# VCO_SCH.net
KiCad netlist of a schematic drawn in Altium Designer
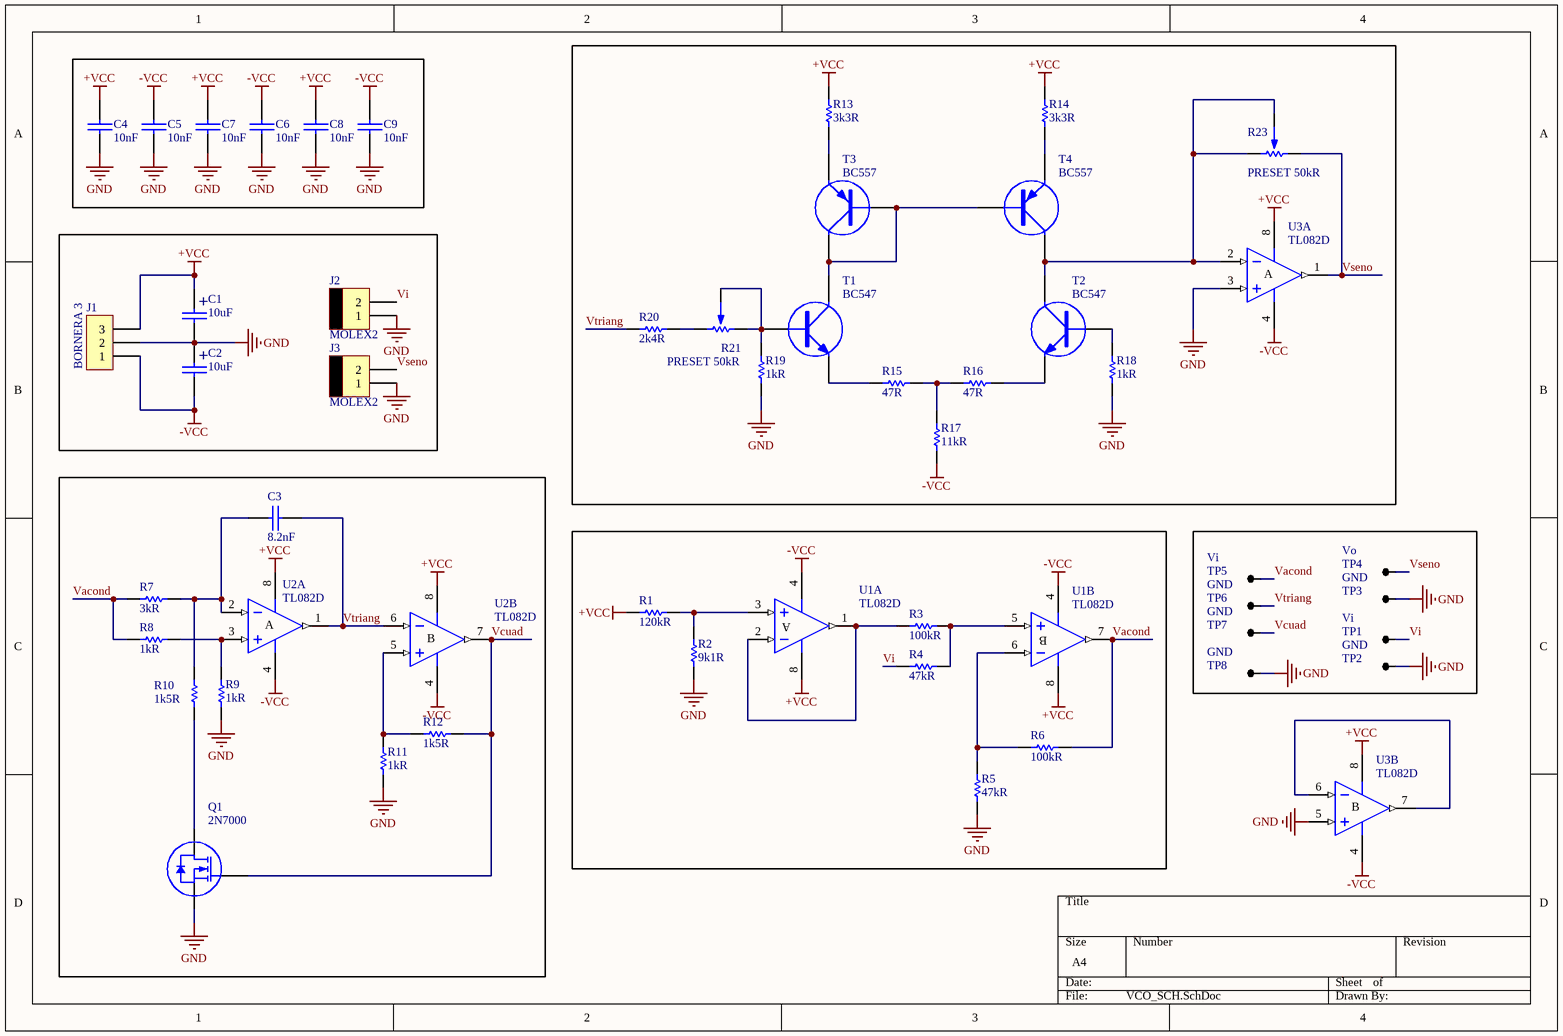
[diagram p0: VCO_SCH.SchDoc]

(export (version "E")
  (design (tool "Eeschema 10.0.6"))
  (components
    (comp (ref "C1") (value "10uF") (footprint "CAP100RP") (libsource (lib "LIBEBAL") (part "CAPPOL")))
    (comp (ref "C2") (value "10uF") (footprint "CAP100RP") (libsource (lib "LIBEBAL") (part "CAPPOL")))
    (comp (ref "C3") (value "8.2nF") (footprint "0805") (libsource (lib "LIBEBAL") (part "CAP")))
    (comp (ref "C4") (value "10nF") (footprint "0805") (libsource (lib "LIBEBAL") (part "CAP")))
    (comp (ref "C5") (value "10nF") (footprint "0805") (libsource (lib "LIBEBAL") (part "CAP")))
    (comp (ref "C6") (value "10nF") (footprint "0805") (libsource (lib "LIBEBAL") (part "CAP")))
    (comp (ref "C7") (value "10nF") (footprint "0805") (libsource (lib "LIBEBAL") (part "CAP")))
    (comp (ref "C8") (value "10nF") (footprint "0805") (libsource (lib "LIBEBAL") (part "CAP")))
    (comp (ref "C9") (value "10nF") (footprint "0805") (libsource (lib "LIBEBAL") (part "CAP")))
    (comp (ref "J1")
      (value "BORNERA 3")
      (footprint "BORNERA3")
      (libsource (lib "LIBEBAL") (part "BORNERA 3"))
    )
    (comp (ref "J2") (value "MOLEX2") (footprint "MOLEX2") (libsource (lib "LIBEBAL") (part "MOLEX2")))
    (comp (ref "J3") (value "MOLEX2") (footprint "MOLEX2") (libsource (lib "LIBEBAL") (part "MOLEX2")))
    (comp (ref "Q1") (value "2N7000") (footprint "TO92") (libsource (lib "LIBEBAL") (part "MOSFET N")))
    (comp (ref "R1") (value "120kR") (footprint "0805") (libsource (lib "LIBEBAL") (part "RES")))
    (comp (ref "R2") (value "9k1R") (footprint "0805") (libsource (lib "LIBEBAL") (part "RES")))
    (comp (ref "R3") (value "100kR") (footprint "0805") (libsource (lib "LIBEBAL") (part "RES")))
    (comp (ref "R4") (value "47kR") (footprint "0805") (libsource (lib "LIBEBAL") (part "RES")))
    (comp (ref "R5") (value "47kR") (footprint "0805") (libsource (lib "LIBEBAL") (part "RES")))
    (comp (ref "R6") (value "100kR") (footprint "0805") (libsource (lib "LIBEBAL") (part "RES")))
    (comp (ref "R7") (value "3kR") (footprint "0805") (libsource (lib "LIBEBAL") (part "RES")))
    (comp (ref "R8") (value "1kR") (footprint "0805") (libsource (lib "LIBEBAL") (part "RES")))
    (comp (ref "R9") (value "1kR") (footprint "0805") (libsource (lib "LIBEBAL") (part "RES")))
    (comp (ref "R10") (value "1k5R") (footprint "0805") (libsource (lib "LIBEBAL") (part "RES")))
    (comp (ref "R11") (value "1kR") (footprint "0805") (libsource (lib "LIBEBAL") (part "RES")))
    (comp (ref "R12") (value "1k5R") (footprint "0805") (libsource (lib "LIBEBAL") (part "RES")))
    (comp (ref "R13") (value "3k3R") (footprint "0805") (libsource (lib "LIBEBAL") (part "RES")))
    (comp (ref "R14") (value "3k3R") (footprint "0805") (libsource (lib "LIBEBAL") (part "RES")))
    (comp (ref "R15") (value "47R") (footprint "0805") (libsource (lib "LIBEBAL") (part "RES")))
    (comp (ref "R16") (value "47R") (footprint "0805") (libsource (lib "LIBEBAL") (part "RES")))
    (comp (ref "R17") (value "11kR") (footprint "0805") (libsource (lib "LIBEBAL") (part "RES")))
    (comp (ref "R18") (value "1kR") (footprint "0805") (libsource (lib "LIBEBAL") (part "RES")))
    (comp (ref "R19") (value "1kR") (footprint "0805") (libsource (lib "LIBEBAL") (part "RES")))
    (comp (ref "R20") (value "2k4R") (footprint "0805") (libsource (lib "LIBEBAL") (part "RES")))
    (comp (ref "R21")
      (value "PRESET 50kR")
      (footprint "PRESET V")
      (libsource (lib "LIBEBAL") (part "PRESET"))
    )
    (comp (ref "R23")
      (value "PRESET 50kR")
      (footprint "PRESET V")
      (libsource (lib "LIBEBAL") (part "PRESET"))
    )
    (comp (ref "T1") (value "BC547") (footprint "TO92") (libsource (lib "LIBEBAL") (part "TRANSISTOR NPN")))
    (comp (ref "T2") (value "BC547") (footprint "TO92") (libsource (lib "LIBEBAL") (part "TRANSISTOR NPN")))
    (comp (ref "T3") (value "BC557") (footprint "TO92") (libsource (lib "LIBEBAL") (part "TRANSISTOR PNP")))
    (comp (ref "T4") (value "BC557") (footprint "TO92") (libsource (lib "LIBEBAL") (part "TRANSISTOR PNP")))
    (comp (ref "TP1") (value "Vi") (footprint "TPTH") (libsource (lib "LIBEBAL") (part "TP")))
    (comp (ref "TP2") (value "GND") (footprint "TPTH") (libsource (lib "LIBEBAL") (part "TP")))
    (comp (ref "TP3") (value "GND") (footprint "TPTH") (libsource (lib "LIBEBAL") (part "TP")))
    (comp (ref "TP4") (value "Vo") (footprint "TPTH") (libsource (lib "LIBEBAL") (part "TP")))
    (comp (ref "TP5") (value "Vi") (footprint "TPTH") (libsource (lib "LIBEBAL") (part "TP")))
    (comp (ref "TP6") (value "GND") (footprint "TPTH") (libsource (lib "LIBEBAL") (part "TP")))
    (comp (ref "TP7") (value "GND") (footprint "TPTH") (libsource (lib "LIBEBAL") (part "TP")))
    (comp (ref "TP8") (value "GND") (footprint "TPTH") (libsource (lib "LIBEBAL") (part "TP")))
    (comp (ref "U1")
      (value "TL082D")
      (footprint "SOIC8")
      (description "JFET-Input Operational Amplifier")
      (libsource (lib "TI Operational Amplifier") (part "TL082D"))
    )
    (comp (ref "U2")
      (value "TL082D")
      (footprint "SOIC8")
      (description "JFET-Input Operational Amplifier")
      (libsource (lib "TI Operational Amplifier") (part "TL082D"))
    )
    (comp (ref "U3")
      (value "TL082D")
      (footprint "SOIC8")
      (description "JFET-Input Operational Amplifier")
      (libsource (lib "TI Operational Amplifier") (part "TL082D"))
    )
  )
  (nets
    (net (code "1") (name "+VCC") (class "Default")
      (node (ref "C1") (pin "1") (pinfunction "1_1") (pintype "passive"))
      (node (ref "C4") (pin "2") (pinfunction "2_2") (pintype "passive"))
      (node (ref "C7") (pin "2") (pinfunction "2_2") (pintype "passive"))
      (node (ref "C8") (pin "2") (pinfunction "2_2") (pintype "passive"))
      (node (ref "J1") (pin "3") (pinfunction "3_3") (pintype "passive"))
      (node (ref "R1") (pin "1") (pinfunction "1_1") (pintype "passive"))
      (node (ref "R13") (pin "1") (pinfunction "1_1") (pintype "passive"))
      (node (ref "R14") (pin "1") (pinfunction "1_1") (pintype "passive"))
      (node (ref "U1") (pin "8") (pinfunction "V+_8") (pintype "power_in"))
      (node (ref "U2") (pin "8") (pinfunction "V+_8") (pintype "power_in"))
      (node (ref "U3") (pin "8") (pinfunction "V+_8") (pintype "power_in"))
    )
    (net (code "2") (name "-VCC") (class "Default")
      (node (ref "C2") (pin "2") (pinfunction "2_2") (pintype "passive"))
      (node (ref "C5") (pin "2") (pinfunction "2_2") (pintype "passive"))
      (node (ref "C6") (pin "2") (pinfunction "2_2") (pintype "passive"))
      (node (ref "C9") (pin "2") (pinfunction "2_2") (pintype "passive"))
      (node (ref "J1") (pin "1") (pinfunction "1_1") (pintype "passive"))
      (node (ref "R17") (pin "1") (pinfunction "1_1") (pintype "passive"))
      (node (ref "U1") (pin "4") (pinfunction "V-_4") (pintype "power_in"))
      (node (ref "U2") (pin "4") (pinfunction "V-_4") (pintype "power_in"))
      (node (ref "U3") (pin "4") (pinfunction "V-_4") (pintype "power_in"))
    )
    (net (code "3") (name "/Vacond") (class "Default")
      (node (ref "R6") (pin "2") (pinfunction "2_2") (pintype "passive"))
      (node (ref "R7") (pin "1") (pinfunction "1_1") (pintype "passive"))
      (node (ref "R8") (pin "1") (pinfunction "1_1") (pintype "passive"))
      (node (ref "TP5") (pin "1") (pinfunction "1_1") (pintype "passive"))
      (node (ref "U1") (pin "7") (pinfunction "OUT_7") (pintype "output"))
    )
    (net (code "4") (name "/Vcuad") (class "Default")
      (node (ref "Q1") (pin "1") (pinfunction "G_1") (pintype "passive"))
      (node (ref "R12") (pin "2") (pinfunction "2_2") (pintype "passive"))
      (node (ref "TP7") (pin "1") (pinfunction "1_1") (pintype "passive"))
      (node (ref "U2") (pin "7") (pinfunction "OUT_7") (pintype "output"))
    )
    (net (code "5") (name "/Vi") (class "Default")
      (node (ref "J2") (pin "2") (pinfunction "2_2") (pintype "passive"))
      (node (ref "R4") (pin "1") (pinfunction "1_1") (pintype "passive"))
      (node (ref "TP1") (pin "1") (pinfunction "1_1") (pintype "passive"))
    )
    (net (code "6") (name "/Vseno") (class "Default")
      (node (ref "J3") (pin "2") (pinfunction "2_2") (pintype "passive"))
      (node (ref "R23") (pin "3") (pinfunction "3_3") (pintype "passive"))
      (node (ref "TP4") (pin "1") (pinfunction "1_1") (pintype "passive"))
      (node (ref "U3") (pin "1") (pinfunction "OUT_1") (pintype "output"))
    )
    (net (code "7") (name "/Vtriang") (class "Default")
      (node (ref "C3") (pin "2") (pinfunction "2_2") (pintype "passive"))
      (node (ref "R20") (pin "1") (pinfunction "1_1") (pintype "passive"))
      (node (ref "TP6") (pin "1") (pinfunction "1_1") (pintype "passive"))
      (node (ref "U2") (pin "1") (pinfunction "OUT_1") (pintype "output"))
      (node (ref "U2") (pin "6") (pinfunction "IN-_6") (pintype "input"))
    )
    (net (code "8") (name "GND") (class "Default")
      (node (ref "C1") (pin "2") (pinfunction "2_2") (pintype "passive"))
      (node (ref "C2") (pin "1") (pinfunction "1_1") (pintype "passive"))
      (node (ref "C4") (pin "1") (pinfunction "1_1") (pintype "passive"))
      (node (ref "C5") (pin "1") (pinfunction "1_1") (pintype "passive"))
      (node (ref "C6") (pin "1") (pinfunction "1_1") (pintype "passive"))
      (node (ref "C7") (pin "1") (pinfunction "1_1") (pintype "passive"))
      (node (ref "C8") (pin "1") (pinfunction "1_1") (pintype "passive"))
      (node (ref "C9") (pin "1") (pinfunction "1_1") (pintype "passive"))
      (node (ref "J1") (pin "2") (pinfunction "2_2") (pintype "passive"))
      (node (ref "J2") (pin "1") (pinfunction "1_1") (pintype "passive"))
      (node (ref "J3") (pin "1") (pinfunction "1_1") (pintype "passive"))
      (node (ref "Q1") (pin "3") (pinfunction "S_3") (pintype "passive"))
      (node (ref "R11") (pin "2") (pinfunction "2_2") (pintype "passive"))
      (node (ref "R18") (pin "1") (pinfunction "1_1") (pintype "passive"))
      (node (ref "R19") (pin "1") (pinfunction "1_1") (pintype "passive"))
      (node (ref "R2") (pin "1") (pinfunction "1_1") (pintype "passive"))
      (node (ref "R5") (pin "1") (pinfunction "1_1") (pintype "passive"))
      (node (ref "R9") (pin "1") (pinfunction "1_1") (pintype "passive"))
      (node (ref "TP2") (pin "1") (pinfunction "1_1") (pintype "passive"))
      (node (ref "TP3") (pin "1") (pinfunction "1_1") (pintype "passive"))
      (node (ref "TP8") (pin "1") (pinfunction "1_1") (pintype "passive"))
      (node (ref "U3") (pin "3") (pinfunction "IN+_3") (pintype "input"))
      (node (ref "U3") (pin "5") (pinfunction "IN+_5") (pintype "input"))
    )
    (net (code "9") (name "Net-(Q1-D)") (class "Default")
      (node (ref "Q1") (pin "2") (pinfunction "D_2") (pintype "passive"))
      (node (ref "R10") (pin "2") (pinfunction "2_2") (pintype "passive"))
    )
    (net (code "10") (name "Net-(R15-Pad2)") (class "Default")
      (node (ref "R15") (pin "2") (pinfunction "2_2") (pintype "passive"))
      (node (ref "R16") (pin "1") (pinfunction "1_1") (pintype "passive"))
      (node (ref "R17") (pin "2") (pinfunction "2_2") (pintype "passive"))
    )
    (net (code "11") (name "Net-(R20-Pad2)") (class "Default")
      (node (ref "R20") (pin "2") (pinfunction "2_2") (pintype "passive"))
      (node (ref "R21") (pin "1") (pinfunction "1_1") (pintype "passive"))
    )
    (net (code "12") (name "Net-(T1-B)") (class "Default")
      (node (ref "R19") (pin "2") (pinfunction "2_2") (pintype "passive"))
      (node (ref "R21") (pin "2") (pinfunction "2_2") (pintype "passive"))
      (node (ref "R21") (pin "3") (pinfunction "3_3") (pintype "passive"))
      (node (ref "T1") (pin "1") (pinfunction "B_1") (pintype "passive"))
    )
    (net (code "13") (name "Net-(T1-C)") (class "Default")
      (node (ref "T1") (pin "2") (pinfunction "C_2") (pintype "passive"))
      (node (ref "T3") (pin "1") (pinfunction "B_1") (pintype "passive"))
      (node (ref "T3") (pin "2") (pinfunction "C_2") (pintype "passive"))
      (node (ref "T4") (pin "1") (pinfunction "B_1") (pintype "passive"))
    )
    (net (code "14") (name "Net-(T1-E)") (class "Default")
      (node (ref "R15") (pin "1") (pinfunction "1_1") (pintype "passive"))
      (node (ref "T1") (pin "3") (pinfunction "E_3") (pintype "passive"))
    )
    (net (code "15") (name "Net-(T2-B)") (class "Default")
      (node (ref "R18") (pin "2") (pinfunction "2_2") (pintype "passive"))
      (node (ref "T2") (pin "1") (pinfunction "B_1") (pintype "passive"))
    )
    (net (code "16") (name "Net-(T2-C)") (class "Default")
      (node (ref "R23") (pin "1") (pinfunction "1_1") (pintype "passive"))
      (node (ref "R23") (pin "2") (pinfunction "2_2") (pintype "passive"))
      (node (ref "T2") (pin "2") (pinfunction "C_2") (pintype "passive"))
      (node (ref "T4") (pin "2") (pinfunction "C_2") (pintype "passive"))
      (node (ref "U3") (pin "2") (pinfunction "IN-_2") (pintype "input"))
    )
    (net (code "17") (name "Net-(T2-E)") (class "Default")
      (node (ref "R16") (pin "2") (pinfunction "2_2") (pintype "passive"))
      (node (ref "T2") (pin "3") (pinfunction "E_3") (pintype "passive"))
    )
    (net (code "18") (name "Net-(T3-E)") (class "Default")
      (node (ref "R13") (pin "2") (pinfunction "2_2") (pintype "passive"))
      (node (ref "T3") (pin "3") (pinfunction "E_3") (pintype "passive"))
    )
    (net (code "19") (name "Net-(T4-E)") (class "Default")
      (node (ref "R14") (pin "2") (pinfunction "2_2") (pintype "passive"))
      (node (ref "T4") (pin "3") (pinfunction "E_3") (pintype "passive"))
    )
    (net (code "20") (name "Net-(U1A-IN+)") (class "Default")
      (node (ref "R1") (pin "2") (pinfunction "2_2") (pintype "passive"))
      (node (ref "R2") (pin "2") (pinfunction "2_2") (pintype "passive"))
      (node (ref "U1") (pin "3") (pinfunction "IN+_3") (pintype "input"))
    )
    (net (code "21") (name "Net-(U1A-IN-)") (class "Default")
      (node (ref "R3") (pin "2") (pinfunction "2_2") (pintype "passive"))
      (node (ref "U1") (pin "1") (pinfunction "OUT_1") (pintype "output"))
      (node (ref "U1") (pin "2") (pinfunction "IN-_2") (pintype "input"))
    )
    (net (code "22") (name "Net-(U1B-IN+)") (class "Default")
      (node (ref "R3") (pin "1") (pinfunction "1_1") (pintype "passive"))
      (node (ref "R4") (pin "2") (pinfunction "2_2") (pintype "passive"))
      (node (ref "U1") (pin "5") (pinfunction "IN+_5") (pintype "input"))
    )
    (net (code "23") (name "Net-(U1B-IN-)") (class "Default")
      (node (ref "R5") (pin "2") (pinfunction "2_2") (pintype "passive"))
      (node (ref "R6") (pin "1") (pinfunction "1_1") (pintype "passive"))
      (node (ref "U1") (pin "6") (pinfunction "IN-_6") (pintype "input"))
    )
    (net (code "24") (name "Net-(U2A-IN+)") (class "Default")
      (node (ref "R8") (pin "2") (pinfunction "2_2") (pintype "passive"))
      (node (ref "R9") (pin "2") (pinfunction "2_2") (pintype "passive"))
      (node (ref "U2") (pin "3") (pinfunction "IN+_3") (pintype "input"))
    )
    (net (code "25") (name "Net-(U2A-IN-)") (class "Default")
      (node (ref "C3") (pin "1") (pinfunction "1_1") (pintype "passive"))
      (node (ref "R10") (pin "1") (pinfunction "1_1") (pintype "passive"))
      (node (ref "R7") (pin "2") (pinfunction "2_2") (pintype "passive"))
      (node (ref "U2") (pin "2") (pinfunction "IN-_2") (pintype "input"))
    )
    (net (code "26") (name "Net-(U2B-IN+)") (class "Default")
      (node (ref "R11") (pin "1") (pinfunction "1_1") (pintype "passive"))
      (node (ref "R12") (pin "1") (pinfunction "1_1") (pintype "passive"))
      (node (ref "U2") (pin "5") (pinfunction "IN+_5") (pintype "input"))
    )
    (net (code "27") (name "Net-(U3B-IN-)") (class "Default")
      (node (ref "U3") (pin "6") (pinfunction "IN-_6") (pintype "input"))
      (node (ref "U3") (pin "7") (pinfunction "OUT_7") (pintype "output"))
    )
  )
)
